# ChassisSupply.net
KiCad netlist of a schematic drawn in EasyEDA Pro
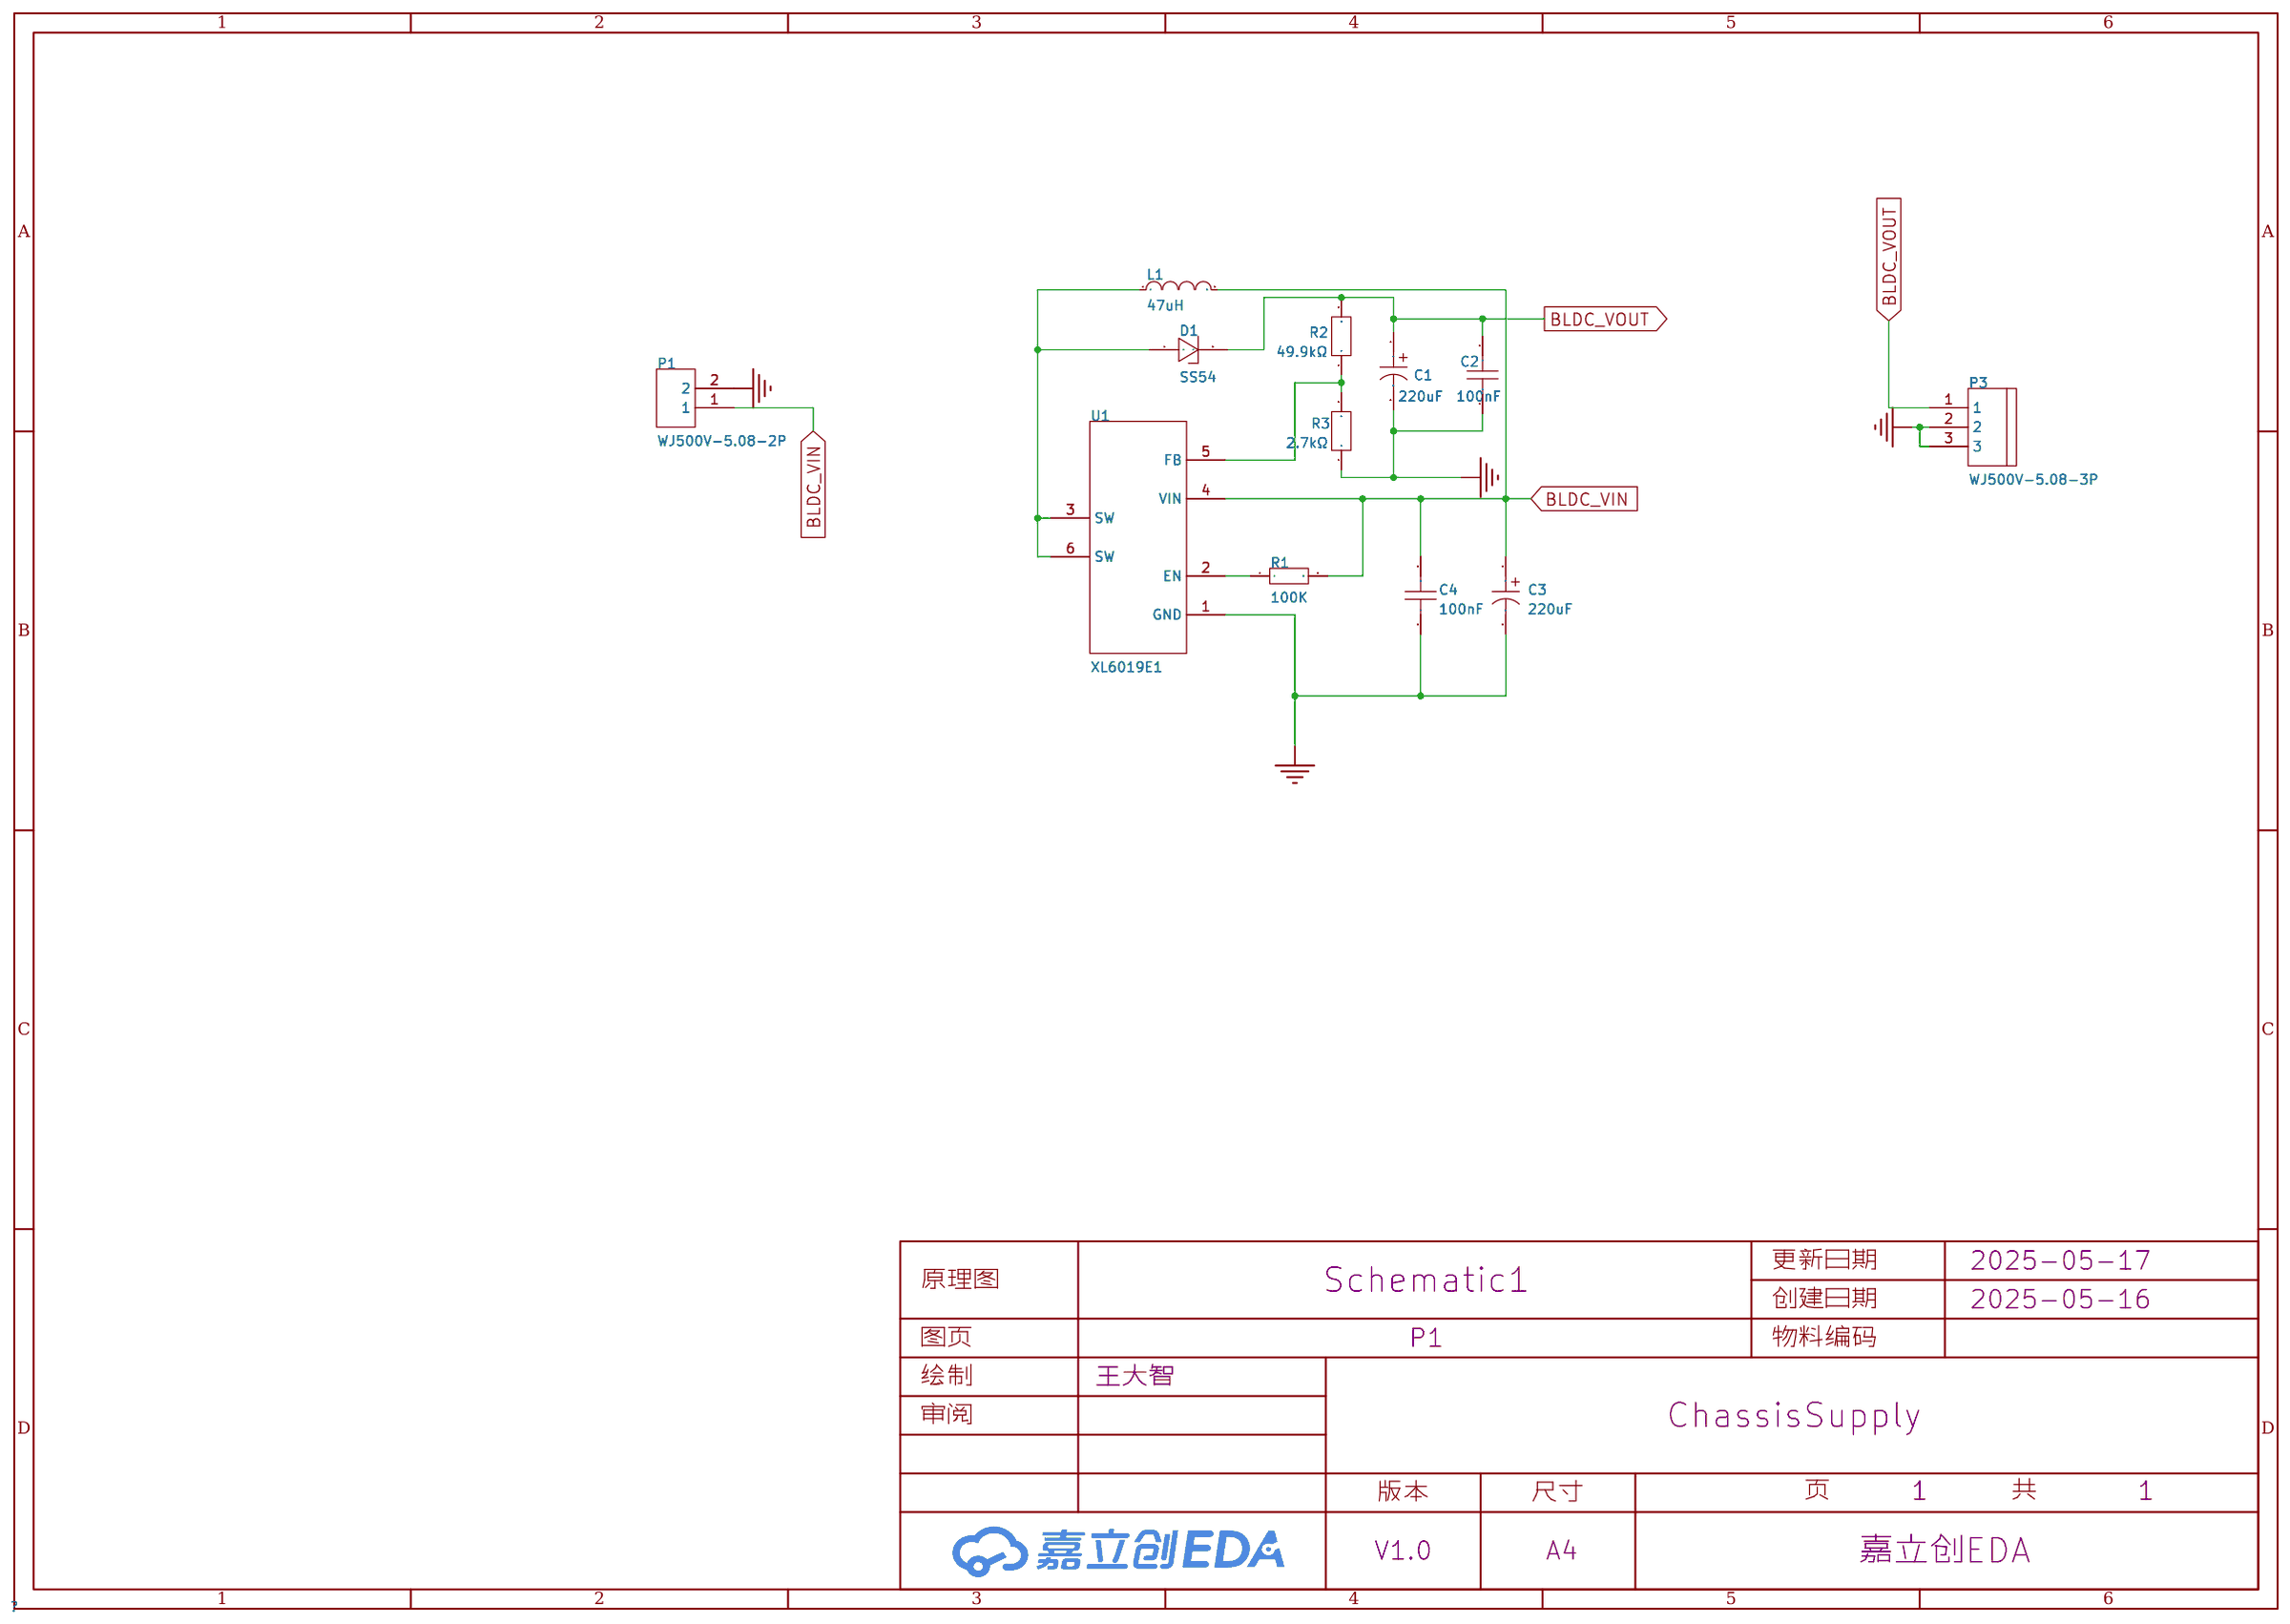
[diagram p0: schematic sheet]

(export (version "E")
  (design (tool "Eeschema 10.0.6"))
  (components
    (comp (ref "C1")
      (value "220uF")
      (footprint "easyedapro:CAP-SMD_BD8.0-L8.3-W8.3-FD")
      (description "容值:220uF;精度:±20%;额定电压:35V;纹波电流:175mA@120Hz;")
      (fields
        (field (name "Manufacturer Part") "GVT1V227M0810CNVC")
        (field (name "Manufacturer") "HRK(鸿瑞凯电子)")
      )
      (libsource (lib "easyedapro") (part "GVT1V227M0810CNVC"))
    )
    (comp (ref "C2")
      (value "100nF")
      (footprint "easyedapro:C0603")
      (libsource (lib "easyedapro") (part "CapAcitance"))
    )
    (comp (ref "C3")
      (value "220uF")
      (footprint "easyedapro:CAP-SMD_BD8.0-L8.3-W8.3-FD")
      (description "容值:220uF;精度:±20%;额定电压:35V;纹波电流:175mA@120Hz;")
      (fields
        (field (name "Manufacturer Part") "GVT1V227M0810CNVC")
        (field (name "Manufacturer") "HRK(鸿瑞凯电子)")
      )
      (libsource (lib "easyedapro") (part "GVT1V227M0810CNVC"))
    )
    (comp (ref "C4")
      (value "100nF")
      (footprint "easyedapro:C0603")
      (libsource (lib "easyedapro") (part "CapAcitance"))
    )
    (comp (ref "D1")
      (value "SS54")
      (footprint "easyedapro:SMA_L4.3-W2.6-LS5.0-FD")
      (description "二极管配置:独立式;正向压降(Vf):550mV@5.0A;直流反向耐压(Vr):40V;整流电流:5A;")
      (fields (field (name "Manufacturer") "宏迦橙"))
      (libsource (lib "easyedapro") (part "SS54_C7420369"))
    )
    (comp (ref "L1")
      (value "47uH")
      (footprint "easyedapro:IND-SMD_L11.5-W10.0_SMMS1040")
      (description "电感值:47uH;精度:±20%;额定电流:3A;饱和电流(Isat):4.5A;类型:一体成型电感;")
      (fields (field (name "Manufacturer Part") "SMMS1040-470M") (field (name "Manufacturer") "SXN(顺翔诺)"))
      (libsource (lib "easyedapro") (part "SMMS1040-470M"))
    )
    (comp (ref "P1")
      (value "WJ500V-5.08-2P")
      (footprint "easyedapro:CONN-TH_2P-P5.00_WJ500V-5.08-2P")
      (fields (field (name "Manufacturer") "KANGNEX(康奈克斯电气)"))
      (libsource (lib "easyedapro") (part "WJ500V-5.08-2P-14-00A"))
    )
    (comp (ref "P3")
      (value "WJ500V-5.08-3P")
      (footprint "easyedapro:CONN-TH_3P-P5.00_WJ500V-5.08-3P")
      (fields (field (name "Manufacturer") "KANGNEX(康奈克斯电气)"))
      (libsource (lib "easyedapro") (part "WJ500V-5.08-3P-14-00A"))
    )
    (comp (ref "R1") (value "100K") (footprint "easyedapro:R0603") (libsource (lib "easyedapro") (part "电阻")))
    (comp (ref "R2")
      (value "49.9kΩ")
      (footprint "easyedapro:R0603")
      (description "电阻类型:厚膜电阻;阻值:49.9kΩ;精度:±1%;功率:100mW;最大工作电压:75V;温度系数:±100ppm/°C;")
      (fields (field (name "Manufacturer Part") "FRC0603F4992TS") (field (name "Manufacturer") "FOJAN(富捷)"))
      (libsource (lib "easyedapro") (part "FRC0603F4992TS"))
    )
    (comp (ref "R3")
      (value "2.7kΩ")
      (footprint "easyedapro:R0603")
      (description "电阻类型:厚膜电阻;阻值:2.7kΩ;精度:±1%;功率:100mW;工作电压:75V;温度系数:±100ppm/°C;")
      (fields (field (name "Manufacturer Part") "FRC0603F2701TS") (field (name "Manufacturer") "FOJAN(富捷)"))
      (libsource (lib "easyedapro") (part "FRC0603F2701TS"))
    )
    (comp (ref "U1")
      (value "XL6019E1")
      (footprint "easyedapro:TO-263-5_L10.2-W9.9-P1.70-LS14.4-TL")
      (description "功能类型:升降压型;输出类型:可调;工作电压:5V~40V;输出电压:-;输出电流:5A;")
      (fields (field (name "Manufacturer") "XLSEMI(芯龙)"))
      (libsource (lib "easyedapro") (part "XL6019E1"))
    )
  )
  (nets
    (net (code "1") (name "BLDC_VIN") (class "Default")
      (node (ref "C3") (pin "1") (pinfunction "1_1") (pintype "input"))
      (node (ref "C4") (pin "1") (pinfunction "1_1") (pintype "input"))
      (node (ref "L1") (pin "2") (pinfunction "2_2") (pintype "unspecified"))
      (node (ref "P1") (pin "1") (pinfunction "1_1") (pintype "unspecified"))
      (node (ref "R1") (pin "2") (pinfunction "2_2") (pintype "input"))
      (node (ref "U1") (pin "4") (pinfunction "VIN_4") (pintype "unspecified"))
    )
    (net (code "2") (name "BLDC_VOUT") (class "Default")
      (node (ref "C1") (pin "1") (pinfunction "1_1") (pintype "input"))
      (node (ref "C2") (pin "2") (pinfunction "2_2") (pintype "input"))
      (node (ref "D1") (pin "2") (pinfunction "K_2") (pintype "unspecified"))
      (node (ref "P3") (pin "1") (pinfunction "1_1") (pintype "unspecified"))
      (node (ref "R2") (pin "2") (pinfunction "2_2") (pintype "unspecified"))
    )
    (net (code "3") (name "GND") (class "Default")
      (node (ref "C1") (pin "2") (pinfunction "2_2") (pintype "input"))
      (node (ref "C2") (pin "1") (pinfunction "1_1") (pintype "input"))
      (node (ref "C3") (pin "2") (pinfunction "2_2") (pintype "input"))
      (node (ref "C4") (pin "2") (pinfunction "2_2") (pintype "input"))
      (node (ref "P1") (pin "2") (pinfunction "2_2") (pintype "unspecified"))
      (node (ref "P3") (pin "2") (pinfunction "2_2") (pintype "unspecified"))
      (node (ref "P3") (pin "3") (pinfunction "3_3") (pintype "unspecified"))
      (node (ref "R3") (pin "1") (pinfunction "1_1") (pintype "unspecified"))
      (node (ref "U1") (pin "1") (pinfunction "GND_1") (pintype "unspecified"))
    )
    (net (code "4") (name "Net-(D1-A)") (class "Default")
      (node (ref "D1") (pin "1") (pinfunction "A_1") (pintype "unspecified"))
      (node (ref "L1") (pin "1") (pinfunction "1_1") (pintype "unspecified"))
      (node (ref "U1") (pin "3") (pinfunction "SW_3") (pintype "unspecified"))
      (node (ref "U1") (pin "6") (pinfunction "SW_6") (pintype "unspecified"))
    )
    (net (code "5") (name "Net-(U1-EN)") (class "Default")
      (node (ref "R1") (pin "1") (pinfunction "1_1") (pintype "input"))
      (node (ref "U1") (pin "2") (pinfunction "EN_2") (pintype "unspecified"))
    )
    (net (code "6") (name "Net-(U1-FB)") (class "Default")
      (node (ref "R2") (pin "1") (pinfunction "1_1") (pintype "unspecified"))
      (node (ref "R3") (pin "2") (pinfunction "2_2") (pintype "unspecified"))
      (node (ref "U1") (pin "5") (pinfunction "FB_5") (pintype "unspecified"))
    )
  )
)
